# thermal_printer.net
KiCad netlist of a schematic drawn in EAGLE
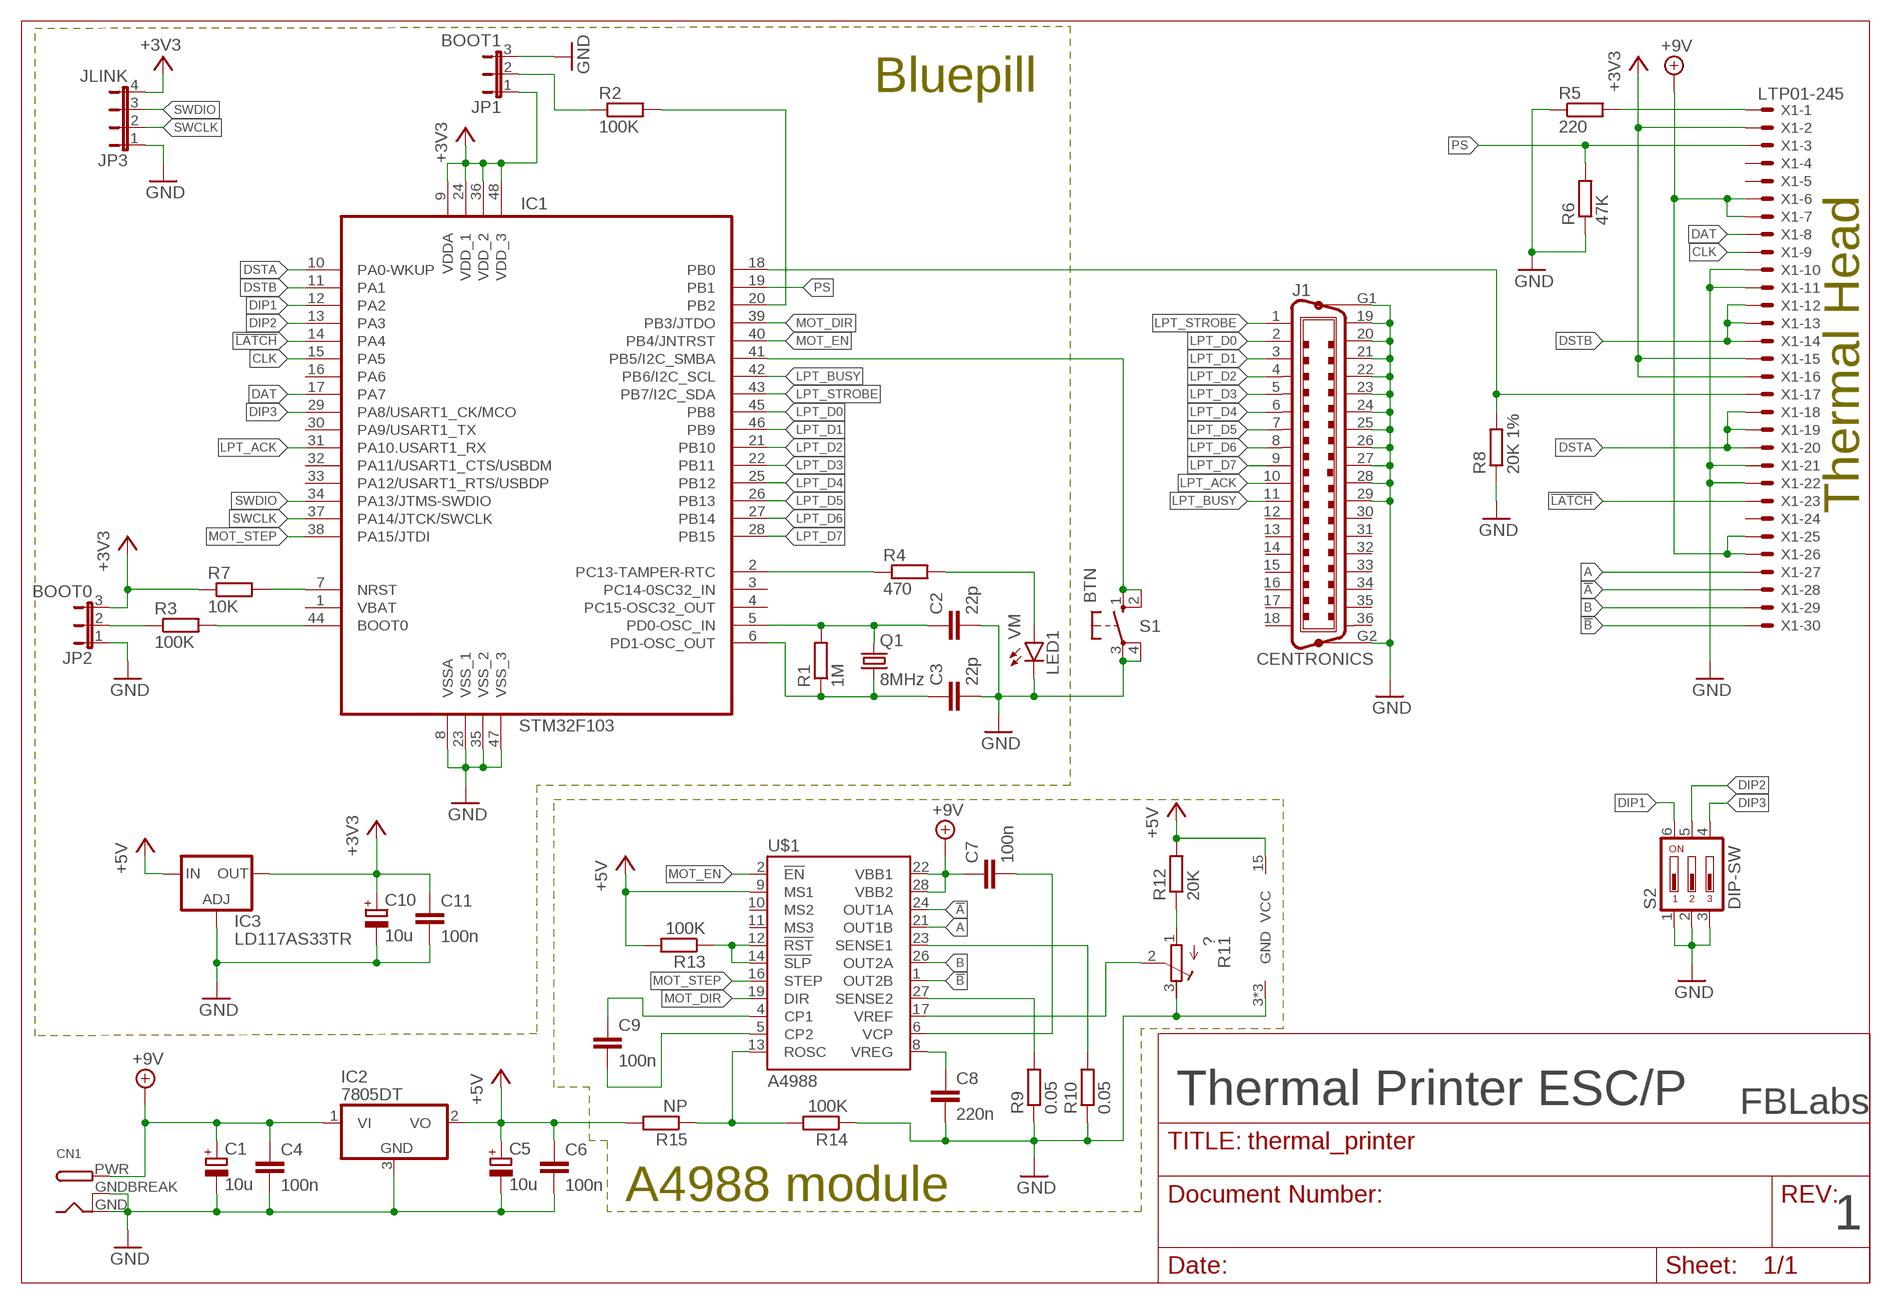
[diagram p0: schematic, sheet 1]

(export (version "E")
  (design (tool "Eeschema 10.0.6"))
  (components
    (comp (ref "C1")
      (value "10u")
      (footprint "eagle-import:PANASONIC_C")
      (libsource (lib "eagle-import") (part "CPOL-EUC"))
    )
    (comp (ref "C2")
      (value "22p")
      (footprint "eagle-import:C1206")
      (libsource (lib "eagle-import") (part "C-EUC1206"))
    )
    (comp (ref "C3")
      (value "22p")
      (footprint "eagle-import:C1206")
      (libsource (lib "eagle-import") (part "C-EUC1206"))
    )
    (comp (ref "C4")
      (value "100n")
      (footprint "eagle-import:C1206")
      (libsource (lib "eagle-import") (part "C-EUC1206"))
    )
    (comp (ref "C5")
      (value "10u")
      (footprint "eagle-import:PANASONIC_C")
      (libsource (lib "eagle-import") (part "CPOL-EUC"))
    )
    (comp (ref "C6")
      (value "100n")
      (footprint "eagle-import:C1206")
      (libsource (lib "eagle-import") (part "C-EUC1206"))
    )
    (comp (ref "C7")
      (value "100n")
      (footprint "eagle-import:C1206")
      (libsource (lib "eagle-import") (part "C-EUC1206"))
    )
    (comp (ref "C8")
      (value "220n")
      (footprint "eagle-import:C1206")
      (libsource (lib "eagle-import") (part "C-EUC1206"))
    )
    (comp (ref "C9")
      (value "100n")
      (footprint "eagle-import:C1206")
      (libsource (lib "eagle-import") (part "C-EUC1206"))
    )
    (comp (ref "C10")
      (value "10u")
      (footprint "eagle-import:PANASONIC_C")
      (libsource (lib "eagle-import") (part "CPOL-EUC"))
    )
    (comp (ref "C11")
      (value "100n")
      (footprint "eagle-import:C1206")
      (libsource (lib "eagle-import") (part "C-EUC1206"))
    )
    (comp (ref "CN1")
      (value "DCBARRELPTH")
      (footprint "eagle-import:DCJACK_2MM_PTH")
      (libsource (lib "eagle-import") (part "DCBARRELPTH"))
    )
    (comp (ref "IC1")
      (value "STM32F103")
      (footprint "eagle-import:LQFP48")
      (libsource (lib "eagle-import") (part "IC_UC_STM32"))
    )
    (comp (ref "IC2")
      (value "7805DT")
      (footprint "eagle-import:TO252")
      (libsource (lib "eagle-import") (part "78DT05"))
    )
    (comp (ref "IC3")
      (value "LD117AS33TR")
      (footprint "eagle-import:SOT223")
      (libsource (lib "eagle-import") (part "LD117A?S33TR"))
    )
    (comp (ref "J1")
      (value "CENTRONICS")
      (footprint "eagle-import:MDR_R_36GH")
      (libsource (lib "eagle-import") (part "MDR_R_36GH"))
    )
    (comp (ref "JP1")
      (value "BOOT1")
      (footprint "eagle-import:JP2")
      (libsource (lib "eagle-import") (part "JP2E"))
    )
    (comp (ref "JP2")
      (value "BOOT0")
      (footprint "eagle-import:JP2")
      (libsource (lib "eagle-import") (part "JP2E"))
    )
    (comp (ref "JP3")
      (value "JLINK")
      (footprint "eagle-import:JP4")
      (libsource (lib "eagle-import") (part "JP4E"))
    )
    (comp (ref "LED1")
      (value "VM")
      (footprint "eagle-import:LED5MM")
      (libsource (lib "eagle-import") (part "LED5MM"))
    )
    (comp (ref "Q1")
      (value "8MHz")
      (footprint "eagle-import:CSM-7X-DU")
      (libsource (lib "eagle-import") (part "CSM-7X-DU"))
    )
    (comp (ref "R1")
      (value "1M")
      (footprint "eagle-import:R1206")
      (libsource (lib "eagle-import") (part "R-EU_R1206"))
    )
    (comp (ref "R2")
      (value "100K")
      (footprint "eagle-import:R1206")
      (libsource (lib "eagle-import") (part "R-EU_R1206"))
    )
    (comp (ref "R3")
      (value "100K")
      (footprint "eagle-import:R1206")
      (libsource (lib "eagle-import") (part "R-EU_R1206"))
    )
    (comp (ref "R4")
      (value "470")
      (footprint "eagle-import:R1206")
      (libsource (lib "eagle-import") (part "R-EU_R1206"))
    )
    (comp (ref "R5")
      (value "220")
      (footprint "eagle-import:R1206")
      (libsource (lib "eagle-import") (part "R-EU_R1206"))
    )
    (comp (ref "R6")
      (value "47K")
      (footprint "eagle-import:R1206")
      (libsource (lib "eagle-import") (part "R-EU_R1206"))
    )
    (comp (ref "R7")
      (value "10K")
      (footprint "eagle-import:R1206")
      (libsource (lib "eagle-import") (part "R-EU_R1206"))
    )
    (comp (ref "R8")
      (value "20K 1%")
      (footprint "eagle-import:R1206")
      (libsource (lib "eagle-import") (part "R-EU_R1206"))
    )
    (comp (ref "R9")
      (value "0.05")
      (footprint "eagle-import:M3216")
      (libsource (lib "eagle-import") (part "rcl_334_R-EU_M3216"))
    )
    (comp (ref "R10")
      (value "0.05")
      (footprint "eagle-import:M3216")
      (libsource (lib "eagle-import") (part "rcl_334_R-EU_M3216"))
    )
    (comp (ref "R11")
      (value "?")
      (footprint "eagle-import:RTRIM4G_J")
      (libsource (lib "eagle-import") (part "R-TRIMM4G/J"))
    )
    (comp (ref "R12")
      (value "20K")
      (footprint "eagle-import:R1206")
      (libsource (lib "eagle-import") (part "R-EU_R1206"))
    )
    (comp (ref "R13")
      (value "100K")
      (footprint "eagle-import:R1206")
      (libsource (lib "eagle-import") (part "R-EU_R1206"))
    )
    (comp (ref "R14")
      (value "100K")
      (footprint "eagle-import:R1206")
      (libsource (lib "eagle-import") (part "R-EU_R1206"))
    )
    (comp (ref "R15")
      (value "NP")
      (footprint "eagle-import:R1206")
      (libsource (lib "eagle-import") (part "R-EU_R1206"))
    )
    (comp (ref "S1")
      (value "BTN")
      (footprint "eagle-import:B3F-10XX")
      (fields (field (name "MPN") "B3F-1000"))
      (libsource (lib "eagle-import") (part "10-XX"))
    )
    (comp (ref "S2")
      (value "DIP-SW")
      (footprint "eagle-import:DA-03")
      (fields (field (name "MPN") "MCDA03"))
      (libsource (lib "eagle-import") (part "DA03"))
    )
    (comp (ref "U$1")
      (value "A4988")
      (footprint "eagle-import:QFN-28-5MM")
      (libsource (lib "eagle-import") (part "A4988"))
    )
    (comp (ref "X1")
      (value "LTP01-245")
      (footprint "eagle-import:52559-3092")
      (fields (field (name "MF") "MOLEX") (field (name "MPN") "52559-3072"))
      (libsource (lib "eagle-import") (part "52559-3092"))
    )
  )
  (nets
    (net (code "1") (name "+3V3") (class "Default")
      (node (ref "C10") (pin "+") (pinfunction "+_+") (pintype "passive"))
      (node (ref "C11") (pin "1") (pinfunction "1_1") (pintype "passive"))
      (node (ref "IC1") (pin "24") (pinfunction "VDD_1_24") (pintype "power_in"))
      (node (ref "IC1") (pin "36") (pinfunction "VDD_2_36") (pintype "power_in"))
      (node (ref "IC1") (pin "48") (pinfunction "VDD_3_48") (pintype "power_in"))
      (node (ref "IC1") (pin "9") (pinfunction "VDDA_9") (pintype "power_in"))
      (node (ref "IC3") (pin "4") (pinfunction "OUT_4") (pintype "passive"))
      (node (ref "JP1") (pin "1") (pinfunction "1_1") (pintype "passive"))
      (node (ref "JP2") (pin "3") (pinfunction "3_3") (pintype "passive"))
      (node (ref "JP3") (pin "4") (pinfunction "4_4") (pintype "passive"))
      (node (ref "R7") (pin "1") (pinfunction "1_1") (pintype "passive"))
      (node (ref "X1") (pin "15") (pinfunction "S_15") (pintype "passive"))
      (node (ref "X1") (pin "16") (pinfunction "S_16") (pintype "passive"))
      (node (ref "X1") (pin "2") (pinfunction "S_2") (pintype "passive"))
    )
    (net (code "2") (name "+5V") (class "Default")
      (node (ref "C5") (pin "+") (pinfunction "+_+") (pintype "passive"))
      (node (ref "C6") (pin "1") (pinfunction "1_1") (pintype "passive"))
      (node (ref "IC2") (pin "2") (pinfunction "VO_2") (pintype "passive"))
      (node (ref "IC3") (pin "3") (pinfunction "IN_3") (pintype "input"))
      (node (ref "R12") (pin "2") (pinfunction "2_2") (pintype "passive"))
      (node (ref "R13") (pin "2") (pinfunction "2_2") (pintype "passive"))
      (node (ref "R15") (pin "2") (pinfunction "2_2") (pintype "passive"))
      (node (ref "U$1") (pin "15") (pinfunction "VCC_15") (pintype "power_in"))
      (node (ref "U$1") (pin "9") (pinfunction "MS1_9") (pintype "passive"))
    )
    (net (code "3") (name "+9V") (class "Default")
      (node (ref "C1") (pin "+") (pinfunction "+_+") (pintype "passive"))
      (node (ref "C4") (pin "1") (pinfunction "1_1") (pintype "passive"))
      (node (ref "C7") (pin "1") (pinfunction "1_1") (pintype "passive"))
      (node (ref "CN1") (pin "PWR") (pinfunction "PWR_PWR") (pintype "power_in"))
      (node (ref "IC2") (pin "1") (pinfunction "VI_1") (pintype "input"))
      (node (ref "U$1") (pin "22") (pinfunction "VBB1_22") (pintype "power_in"))
      (node (ref "U$1") (pin "28") (pinfunction "VBB2_28") (pintype "power_in"))
      (node (ref "X1") (pin "25") (pinfunction "S_25") (pintype "passive"))
      (node (ref "X1") (pin "26") (pinfunction "S_26") (pintype "passive"))
      (node (ref "X1") (pin "6") (pinfunction "S_6") (pintype "passive"))
      (node (ref "X1") (pin "7") (pinfunction "S_7") (pintype "passive"))
    )
    (net (code "4") (name "/~{A}") (class "Default")
      (node (ref "U$1") (pin "24") (pinfunction "OUT1A_24") (pintype "output"))
      (node (ref "X1") (pin "28") (pinfunction "S_28") (pintype "passive"))
    )
    (net (code "5") (name "/~{B}") (class "Default")
      (node (ref "U$1") (pin "1") (pinfunction "OUT2B_1") (pintype "output"))
      (node (ref "X1") (pin "30") (pinfunction "S_30") (pintype "passive"))
    )
    (net (code "6") (name "/~{LATCH}") (class "Default")
      (node (ref "IC1") (pin "14") (pinfunction "PA4_14") (pintype "bidirectional"))
      (node (ref "X1") (pin "23") (pinfunction "S_23") (pintype "passive"))
    )
    (net (code "7") (name "A") (class "Default")
      (node (ref "U$1") (pin "21") (pinfunction "OUT1B_21") (pintype "output"))
      (node (ref "X1") (pin "27") (pinfunction "S_27") (pintype "passive"))
    )
    (net (code "8") (name "B") (class "Default")
      (node (ref "U$1") (pin "26") (pinfunction "OUT2A_26") (pintype "output"))
      (node (ref "X1") (pin "29") (pinfunction "S_29") (pintype "passive"))
    )
    (net (code "9") (name "CLK") (class "Default")
      (node (ref "IC1") (pin "15") (pinfunction "PA5_15") (pintype "bidirectional"))
      (node (ref "X1") (pin "9") (pinfunction "S_9") (pintype "passive"))
    )
    (net (code "10") (name "DAT") (class "Default")
      (node (ref "IC1") (pin "17") (pinfunction "PA7_17") (pintype "bidirectional"))
      (node (ref "X1") (pin "8") (pinfunction "S_8") (pintype "passive"))
    )
    (net (code "11") (name "DIP1") (class "Default")
      (node (ref "IC1") (pin "12") (pinfunction "PA2_12") (pintype "bidirectional"))
      (node (ref "S2") (pin "6") (pinfunction "6_6") (pintype "passive"))
    )
    (net (code "12") (name "DIP2") (class "Default")
      (node (ref "IC1") (pin "13") (pinfunction "PA3_13") (pintype "bidirectional"))
      (node (ref "S2") (pin "5") (pinfunction "5_5") (pintype "passive"))
    )
    (net (code "13") (name "DIP3") (class "Default")
      (node (ref "IC1") (pin "29") (pinfunction "PA8/USART1_CK/MCO_29") (pintype "bidirectional"))
      (node (ref "S2") (pin "4") (pinfunction "4_4") (pintype "passive"))
    )
    (net (code "14") (name "DSTA") (class "Default")
      (node (ref "IC1") (pin "10") (pinfunction "PA0-WKUP_10") (pintype "bidirectional"))
      (node (ref "X1") (pin "18") (pinfunction "S_18") (pintype "passive"))
      (node (ref "X1") (pin "19") (pinfunction "S_19") (pintype "passive"))
      (node (ref "X1") (pin "20") (pinfunction "S_20") (pintype "passive"))
    )
    (net (code "15") (name "DSTB") (class "Default")
      (node (ref "IC1") (pin "11") (pinfunction "PA1_11") (pintype "bidirectional"))
      (node (ref "X1") (pin "12") (pinfunction "S_12") (pintype "passive"))
      (node (ref "X1") (pin "13") (pinfunction "S_13") (pintype "passive"))
      (node (ref "X1") (pin "14") (pinfunction "S_14") (pintype "passive"))
    )
    (net (code "16") (name "GND") (class "Default")
      (node (ref "C1") (pin "-") (pinfunction "-_-") (pintype "passive"))
      (node (ref "C10") (pin "-") (pinfunction "-_-") (pintype "passive"))
      (node (ref "C11") (pin "2") (pinfunction "2_2") (pintype "passive"))
      (node (ref "C2") (pin "2") (pinfunction "2_2") (pintype "passive"))
      (node (ref "C3") (pin "2") (pinfunction "2_2") (pintype "passive"))
      (node (ref "C4") (pin "2") (pinfunction "2_2") (pintype "passive"))
      (node (ref "C5") (pin "-") (pinfunction "-_-") (pintype "passive"))
      (node (ref "C6") (pin "2") (pinfunction "2_2") (pintype "passive"))
      (node (ref "C8") (pin "2") (pinfunction "2_2") (pintype "passive"))
      (node (ref "CN1") (pin "GND") (pinfunction "GND_GND") (pintype "power_in"))
      (node (ref "CN1") (pin "GNDBREAK") (pinfunction "GNDBREAK_GNDBREAK") (pintype "power_in"))
      (node (ref "IC1") (pin "23") (pinfunction "VSS_1_23") (pintype "power_in"))
      (node (ref "IC1") (pin "35") (pinfunction "VSS_2_35") (pintype "power_in"))
      (node (ref "IC1") (pin "47") (pinfunction "VSS_3_47") (pintype "power_in"))
      (node (ref "IC1") (pin "8") (pinfunction "VSSA_8") (pintype "power_in"))
      (node (ref "IC2") (pin "3") (pinfunction "GND_3") (pintype "passive"))
      (node (ref "IC3") (pin "1") (pinfunction "ADJ_1") (pintype "input"))
      (node (ref "J1") (pin "19") (pinfunction "19_19") (pintype "passive"))
      (node (ref "J1") (pin "20") (pinfunction "20_20") (pintype "passive"))
      (node (ref "J1") (pin "21") (pinfunction "21_21") (pintype "passive"))
      (node (ref "J1") (pin "22") (pinfunction "22_22") (pintype "passive"))
      (node (ref "J1") (pin "23") (pinfunction "23_23") (pintype "passive"))
      (node (ref "J1") (pin "24") (pinfunction "24_24") (pintype "passive"))
      (node (ref "J1") (pin "25") (pinfunction "25_25") (pintype "passive"))
      (node (ref "J1") (pin "26") (pinfunction "26_26") (pintype "passive"))
      (node (ref "J1") (pin "27") (pinfunction "27_27") (pintype "passive"))
      (node (ref "J1") (pin "28") (pinfunction "28_28") (pintype "passive"))
      (node (ref "J1") (pin "29") (pinfunction "29_29") (pintype "passive"))
      (node (ref "J1") (pin "G1") (pinfunction "G_G1") (pintype "passive"))
      (node (ref "J1") (pin "G2") (pinfunction "G1_G2") (pintype "passive"))
      (node (ref "JP1") (pin "3") (pinfunction "3_3") (pintype "passive"))
      (node (ref "JP2") (pin "1") (pinfunction "1_1") (pintype "passive"))
      (node (ref "JP3") (pin "1") (pinfunction "1_1") (pintype "passive"))
      (node (ref "LED1") (pin "K") (pinfunction "C_K") (pintype "passive"))
      (node (ref "R10") (pin "1") (pinfunction "1_1") (pintype "passive"))
      (node (ref "R11") (pin "3") (pinfunction "E_3") (pintype "passive"))
      (node (ref "R14") (pin "1") (pinfunction "1_1") (pintype "passive"))
      (node (ref "R5") (pin "1") (pinfunction "1_1") (pintype "passive"))
      (node (ref "R6") (pin "1") (pinfunction "1_1") (pintype "passive"))
      (node (ref "R8") (pin "1") (pinfunction "1_1") (pintype "passive"))
      (node (ref "R9") (pin "1") (pinfunction "1_1") (pintype "passive"))
      (node (ref "S1") (pin "3") (pinfunction "P_3") (pintype "passive"))
      (node (ref "S1") (pin "4") (pinfunction "P1_4") (pintype "passive"))
      (node (ref "S2") (pin "1") (pinfunction "1_1") (pintype "passive"))
      (node (ref "S2") (pin "2") (pinfunction "2_2") (pintype "passive"))
      (node (ref "S2") (pin "3") (pinfunction "3_3") (pintype "passive"))
      (node (ref "U$1") (pin "18") (pinfunction "GND_18") (pintype "power_in"))
      (node (ref "U$1") (pin "3") (pinfunction "GND_3") (pintype "power_in"))
      (node (ref "U$1") (pin "PAD") (pinfunction "GND_PAD") (pintype "power_in"))
      (node (ref "X1") (pin "10") (pinfunction "S_10") (pintype "passive"))
      (node (ref "X1") (pin "11") (pinfunction "S_11") (pintype "passive"))
      (node (ref "X1") (pin "21") (pinfunction "S_21") (pintype "passive"))
      (node (ref "X1") (pin "22") (pinfunction "S_22") (pintype "passive"))
    )
    (net (code "17") (name "LPT_ACK") (class "Default")
      (node (ref "IC1") (pin "31") (pinfunction "PA10.USART1_RX_31") (pintype "bidirectional"))
      (node (ref "J1") (pin "10") (pinfunction "10_10") (pintype "passive"))
    )
    (net (code "18") (name "LPT_BUSY") (class "Default")
      (node (ref "IC1") (pin "42") (pinfunction "PB6/I2C_SCL_42") (pintype "bidirectional"))
      (node (ref "J1") (pin "11") (pinfunction "11_11") (pintype "passive"))
    )
    (net (code "19") (name "LPT_D0") (class "Default")
      (node (ref "IC1") (pin "45") (pinfunction "PB8_45") (pintype "bidirectional"))
      (node (ref "J1") (pin "2") (pinfunction "2_2") (pintype "passive"))
    )
    (net (code "20") (name "LPT_D1") (class "Default")
      (node (ref "IC1") (pin "46") (pinfunction "PB9_46") (pintype "bidirectional"))
      (node (ref "J1") (pin "3") (pinfunction "3_3") (pintype "passive"))
    )
    (net (code "21") (name "LPT_D2") (class "Default")
      (node (ref "IC1") (pin "21") (pinfunction "PB10_21") (pintype "bidirectional"))
      (node (ref "J1") (pin "4") (pinfunction "4_4") (pintype "passive"))
    )
    (net (code "22") (name "LPT_D3") (class "Default")
      (node (ref "IC1") (pin "22") (pinfunction "PB11_22") (pintype "bidirectional"))
      (node (ref "J1") (pin "5") (pinfunction "5_5") (pintype "passive"))
    )
    (net (code "23") (name "LPT_D4") (class "Default")
      (node (ref "IC1") (pin "25") (pinfunction "PB12_25") (pintype "bidirectional"))
      (node (ref "J1") (pin "6") (pinfunction "6_6") (pintype "passive"))
    )
    (net (code "24") (name "LPT_D5") (class "Default")
      (node (ref "IC1") (pin "26") (pinfunction "PB13_26") (pintype "bidirectional"))
      (node (ref "J1") (pin "7") (pinfunction "7_7") (pintype "passive"))
    )
    (net (code "25") (name "LPT_D6") (class "Default")
      (node (ref "IC1") (pin "27") (pinfunction "PB14_27") (pintype "bidirectional"))
      (node (ref "J1") (pin "8") (pinfunction "8_8") (pintype "passive"))
    )
    (net (code "26") (name "LPT_D7") (class "Default")
      (node (ref "IC1") (pin "28") (pinfunction "PB15_28") (pintype "bidirectional"))
      (node (ref "J1") (pin "9") (pinfunction "9_9") (pintype "passive"))
    )
    (net (code "27") (name "LPT_STROBE") (class "Default")
      (node (ref "IC1") (pin "43") (pinfunction "PB7/I2C_SDA_43") (pintype "bidirectional"))
      (node (ref "J1") (pin "1") (pinfunction "1_1") (pintype "passive"))
    )
    (net (code "28") (name "MOT_DIR") (class "Default")
      (node (ref "IC1") (pin "39") (pinfunction "PB3/JTDO_39") (pintype "bidirectional"))
      (node (ref "U$1") (pin "19") (pinfunction "DIR_19") (pintype "input"))
    )
    (net (code "29") (name "MOT_EN") (class "Default")
      (node (ref "IC1") (pin "40") (pinfunction "PB4/JNTRST_40") (pintype "bidirectional"))
      (node (ref "U$1") (pin "2") (pinfunction "~{EN}_2") (pintype "passive"))
    )
    (net (code "30") (name "MOT_STEP") (class "Default")
      (node (ref "IC1") (pin "38") (pinfunction "PA15/JTDI_38") (pintype "bidirectional"))
      (node (ref "U$1") (pin "16") (pinfunction "STEP_16") (pintype "input"))
    )
    (net (code "31") (name "Net-(IC1-BOOT0)") (class "Default")
      (node (ref "IC1") (pin "44") (pinfunction "BOOT0_44") (pintype "bidirectional"))
      (node (ref "R3") (pin "2") (pinfunction "2_2") (pintype "passive"))
    )
    (net (code "32") (name "Net-(IC1-NRST)") (class "Default")
      (node (ref "IC1") (pin "7") (pinfunction "NRST_7") (pintype "bidirectional"))
      (node (ref "R7") (pin "2") (pinfunction "2_2") (pintype "passive"))
    )
    (net (code "33") (name "Net-(IC1-PB0)") (class "Default")
      (node (ref "IC1") (pin "18") (pinfunction "PB0_18") (pintype "bidirectional"))
      (node (ref "R8") (pin "2") (pinfunction "2_2") (pintype "passive"))
      (node (ref "X1") (pin "17") (pinfunction "S_17") (pintype "passive"))
    )
    (net (code "34") (name "Net-(IC1-PB2)") (class "Default")
      (node (ref "IC1") (pin "20") (pinfunction "PB2_20") (pintype "bidirectional"))
      (node (ref "R2") (pin "2") (pinfunction "2_2") (pintype "passive"))
    )
    (net (code "35") (name "Net-(IC1-PB5{slash}I2C_SMBA)") (class "Default")
      (node (ref "IC1") (pin "41") (pinfunction "PB5/I2C_SMBA_41") (pintype "bidirectional"))
      (node (ref "S1") (pin "1") (pinfunction "S_1") (pintype "passive"))
      (node (ref "S1") (pin "2") (pinfunction "S1_2") (pintype "passive"))
    )
    (net (code "36") (name "Net-(IC1-PC13-TAMPER-RTC)") (class "Default")
      (node (ref "IC1") (pin "2") (pinfunction "PC13-TAMPER-RTC_2") (pintype "bidirectional"))
      (node (ref "R4") (pin "1") (pinfunction "1_1") (pintype "passive"))
    )
    (net (code "37") (name "Net-(IC1-PD0-OSC_IN)") (class "Default")
      (node (ref "C2") (pin "1") (pinfunction "1_1") (pintype "passive"))
      (node (ref "IC1") (pin "5") (pinfunction "PD0-OSC_IN_5") (pintype "bidirectional"))
      (node (ref "Q1") (pin "2") (pinfunction "2_2") (pintype "passive"))
      (node (ref "R1") (pin "2") (pinfunction "2_2") (pintype "passive"))
    )
    (net (code "38") (name "Net-(IC1-PD1-OSC_OUT)") (class "Default")
      (node (ref "C3") (pin "1") (pinfunction "1_1") (pintype "passive"))
      (node (ref "IC1") (pin "6") (pinfunction "PD1-OSC_OUT_6") (pintype "bidirectional"))
      (node (ref "Q1") (pin "1") (pinfunction "1_1") (pintype "passive"))
      (node (ref "R1") (pin "1") (pinfunction "1_1") (pintype "passive"))
    )
    (net (code "39") (name "Net-(JP1-Pad2)") (class "Default")
      (node (ref "JP1") (pin "2") (pinfunction "2_2") (pintype "passive"))
      (node (ref "R2") (pin "1") (pinfunction "1_1") (pintype "passive"))
    )
    (net (code "40") (name "Net-(JP2-Pad2)") (class "Default")
      (node (ref "JP2") (pin "2") (pinfunction "2_2") (pintype "passive"))
      (node (ref "R3") (pin "1") (pinfunction "1_1") (pintype "passive"))
    )
    (net (code "41") (name "Net-(LED1-PadA)") (class "Default")
      (node (ref "LED1") (pin "A") (pinfunction "A_A") (pintype "passive"))
      (node (ref "R4") (pin "2") (pinfunction "2_2") (pintype "passive"))
    )
    (net (code "42") (name "Net-(R11-A)") (class "Default")
      (node (ref "R11") (pin "1") (pinfunction "A_1") (pintype "passive"))
      (node (ref "R12") (pin "1") (pinfunction "1_1") (pintype "passive"))
    )
    (net (code "43") (name "Net-(R11-S)") (class "Default")
      (node (ref "R11") (pin "2") (pinfunction "S_2") (pintype "passive"))
      (node (ref "U$1") (pin "17") (pinfunction "VREF_17") (pintype "power_in"))
    )
    (net (code "44") (name "Net-(U$1A-CP1)") (class "Default")
      (node (ref "C9") (pin "1") (pinfunction "1_1") (pintype "passive"))
      (node (ref "U$1") (pin "4") (pinfunction "CP1_4") (pintype "bidirectional"))
    )
    (net (code "45") (name "Net-(U$1A-CP2)") (class "Default")
      (node (ref "C9") (pin "2") (pinfunction "2_2") (pintype "passive"))
      (node (ref "U$1") (pin "5") (pinfunction "CP2_5") (pintype "bidirectional"))
    )
    (net (code "46") (name "Net-(U$1A-ROSC)") (class "Default")
      (node (ref "R14") (pin "2") (pinfunction "2_2") (pintype "passive"))
      (node (ref "R15") (pin "1") (pinfunction "1_1") (pintype "passive"))
      (node (ref "U$1") (pin "13") (pinfunction "ROSC_13") (pintype "power_in"))
    )
    (net (code "47") (name "Net-(U$1A-SENSE1)") (class "Default")
      (node (ref "R10") (pin "2") (pinfunction "2_2") (pintype "passive"))
      (node (ref "U$1") (pin "23") (pinfunction "SENSE1_23") (pintype "open_collector"))
    )
    (net (code "48") (name "Net-(U$1A-SENSE2)") (class "Default")
      (node (ref "R9") (pin "2") (pinfunction "2_2") (pintype "passive"))
      (node (ref "U$1") (pin "27") (pinfunction "SENSE2_27") (pintype "open_collector"))
    )
    (net (code "49") (name "Net-(U$1A-VCP)") (class "Default")
      (node (ref "C7") (pin "2") (pinfunction "2_2") (pintype "passive"))
      (node (ref "U$1") (pin "6") (pinfunction "VCP_6") (pintype "power_in"))
    )
    (net (code "50") (name "Net-(U$1A-VREG)") (class "Default")
      (node (ref "C8") (pin "1") (pinfunction "1_1") (pintype "passive"))
      (node (ref "U$1") (pin "8") (pinfunction "VREG_8") (pintype "power_in"))
    )
    (net (code "51") (name "Net-(U$1A-~{RST})") (class "Default")
      (node (ref "R13") (pin "1") (pinfunction "1_1") (pintype "passive"))
      (node (ref "U$1") (pin "12") (pinfunction "~{RST}_12") (pintype "passive"))
      (node (ref "U$1") (pin "14") (pinfunction "~{SLP}_14") (pintype "passive"))
    )
    (net (code "52") (name "Net-(X1A-S)") (class "Default")
      (node (ref "R5") (pin "2") (pinfunction "2_2") (pintype "passive"))
      (node (ref "X1") (pin "1") (pinfunction "S_1") (pintype "passive"))
    )
    (net (code "53") (name "PS") (class "Default")
      (node (ref "IC1") (pin "19") (pinfunction "PB1_19") (pintype "bidirectional"))
      (node (ref "R6") (pin "2") (pinfunction "2_2") (pintype "passive"))
      (node (ref "X1") (pin "3") (pinfunction "S_3") (pintype "passive"))
    )
    (net (code "54") (name "SWCLK") (class "Default")
      (node (ref "IC1") (pin "37") (pinfunction "PA14/JTCK/SWCLK_37") (pintype "bidirectional"))
      (node (ref "JP3") (pin "2") (pinfunction "2_2") (pintype "passive"))
    )
    (net (code "55") (name "SWDIO") (class "Default")
      (node (ref "IC1") (pin "34") (pinfunction "PA13/JTMS-SWDIO_34") (pintype "bidirectional"))
      (node (ref "JP3") (pin "3") (pinfunction "3_3") (pintype "passive"))
    )
    (net (code "56") (name "unconnected-(IC1-PA6-Pad16)") (class "Default")
      (node (ref "IC1") (pin "16") (pinfunction "PA6_16") (pintype "bidirectional"))
    )
    (net (code "57") (name "unconnected-(IC1-PA9{slash}USART1_TX-Pad30)") (class "Default")
      (node (ref "IC1") (pin "30") (pinfunction "PA9/USART1_TX_30") (pintype "bidirectional"))
    )
    (net (code "58") (name "unconnected-(IC1-PA11{slash}USART1_CTS{slash}USBDM-Pad32)") (class "Default")
      (node (ref "IC1") (pin "32") (pinfunction "PA11/USART1_CTS/USBDM_32") (pintype "bidirectional"))
    )
    (net (code "59") (name "unconnected-(IC1-PA12{slash}USART1_RTS{slash}USBDP-Pad33)") (class "Default")
      (node (ref "IC1") (pin "33") (pinfunction "PA12/USART1_RTS/USBDP_33") (pintype "bidirectional"))
    )
    (net (code "60") (name "unconnected-(IC1-PC14-0SC32_IN-Pad3)") (class "Default")
      (node (ref "IC1") (pin "3") (pinfunction "PC14-0SC32_IN_3") (pintype "bidirectional"))
    )
    (net (code "61") (name "unconnected-(IC1-PC15-OSC32_OUT-Pad4)") (class "Default")
      (node (ref "IC1") (pin "4") (pinfunction "PC15-OSC32_OUT_4") (pintype "bidirectional"))
    )
    (net (code "62") (name "unconnected-(IC1-VBAT-Pad1)") (class "Default")
      (node (ref "IC1") (pin "1") (pinfunction "VBAT_1") (pintype "bidirectional"))
    )
    (net (code "63") (name "unconnected-(J1-Pad12)") (class "Default")
      (node (ref "J1") (pin "12") (pinfunction "12_12") (pintype "passive"))
    )
    (net (code "64") (name "unconnected-(J1-Pad13)") (class "Default")
      (node (ref "J1") (pin "13") (pinfunction "13_13") (pintype "passive"))
    )
    (net (code "65") (name "unconnected-(J1-Pad14)") (class "Default")
      (node (ref "J1") (pin "14") (pinfunction "14_14") (pintype "passive"))
    )
    (net (code "66") (name "unconnected-(J1-Pad15)") (class "Default")
      (node (ref "J1") (pin "15") (pinfunction "15_15") (pintype "passive"))
    )
    (net (code "67") (name "unconnected-(J1-Pad16)") (class "Default")
      (node (ref "J1") (pin "16") (pinfunction "16_16") (pintype "passive"))
    )
    (net (code "68") (name "unconnected-(J1-Pad17)") (class "Default")
      (node (ref "J1") (pin "17") (pinfunction "17_17") (pintype "passive"))
    )
    (net (code "69") (name "unconnected-(J1-Pad18)") (class "Default")
      (node (ref "J1") (pin "18") (pinfunction "18_18") (pintype "passive"))
    )
    (net (code "70") (name "unconnected-(J1-Pad30)") (class "Default")
      (node (ref "J1") (pin "30") (pinfunction "30_30") (pintype "passive"))
    )
    (net (code "71") (name "unconnected-(J1-Pad31)") (class "Default")
      (node (ref "J1") (pin "31") (pinfunction "31_31") (pintype "passive"))
    )
    (net (code "72") (name "unconnected-(J1-Pad32)") (class "Default")
      (node (ref "J1") (pin "32") (pinfunction "32_32") (pintype "passive"))
    )
    (net (code "73") (name "unconnected-(J1-Pad33)") (class "Default")
      (node (ref "J1") (pin "33") (pinfunction "33_33") (pintype "passive"))
    )
    (net (code "74") (name "unconnected-(J1-Pad34)") (class "Default")
      (node (ref "J1") (pin "34") (pinfunction "34_34") (pintype "passive"))
    )
    (net (code "75") (name "unconnected-(J1-Pad35)") (class "Default")
      (node (ref "J1") (pin "35") (pinfunction "35_35") (pintype "passive"))
    )
    (net (code "76") (name "unconnected-(J1-Pad36)") (class "Default")
      (node (ref "J1") (pin "36") (pinfunction "36_36") (pintype "passive"))
    )
    (net (code "77") (name "unconnected-(U$1A-MS2-Pad10)") (class "Default")
      (node (ref "U$1") (pin "10") (pinfunction "MS2_10") (pintype "passive"))
    )
    (net (code "78") (name "unconnected-(U$1A-MS3-Pad11)") (class "Default")
      (node (ref "U$1") (pin "11") (pinfunction "MS3_11") (pintype "passive"))
    )
    (net (code "79") (name "unconnected-(X1Q-S-Pad24)") (class "Default")
      (node (ref "X1") (pin "24") (pinfunction "S_24") (pintype "passive"))
    )
    (net (code "80") (name "unconnected-(X1Y-S-Pad4)") (class "Default")
      (node (ref "X1") (pin "4") (pinfunction "S_4") (pintype "passive"))
    )
    (net (code "81") (name "unconnected-(X1Z-S-Pad5)") (class "Default")
      (node (ref "X1") (pin "5") (pinfunction "S_5") (pintype "passive"))
    )
  )
)
